# OptoIsolator.net
KiCad netlist of a schematic drawn in Altium Designer
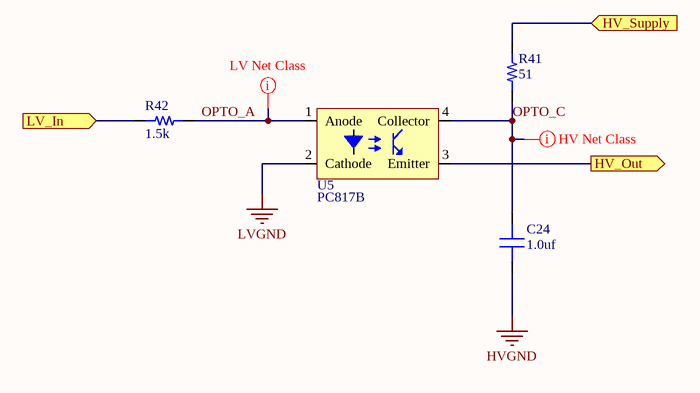
[diagram p0: OptoIsolator.SchDoc]

(export (version "E")
  (design (tool "Eeschema 10.0.6"))
  (components
    (comp (ref "C24")
      (value "1.0uf")
      (footprint "CAP 0603/1608")
      (fields
        (field (name "Comment") "Capacitor MLCC 1.0uf 25V CAP 0603/1608")
        (field (name "CREATED_BY") "Nick Mah")
      )
      (libsource (lib "Altium-Lib") (part "Capacitor"))
    )
    (comp (ref "R41")
      (value "51")
      (footprint "RES 0805/2012")
      (fields
        (field (name "TOLERANCE") "1%")
        (field (name "POWER") "1/4W")
        (field (name "Comment") "Resistor 51 0805 1/4W 1%")
        (field (name "CREATED_BY") "Nick Mah")
      )
      (libsource (lib "Altium-Lib") (part "Resistor"))
    )
    (comp (ref "R42")
      (value "1.5k")
      (footprint "RES 0603/1608")
      (fields
        (field (name "TOLERANCE") "1%")
        (field (name "POWER") "1/10W")
        (field (name "Comment") "Resistor 1.5k 0603 1/10W 1%")
        (field (name "CREATED_BY") "Nick Mah")
      )
      (libsource (lib "Altium-Lib") (part "Resistor"))
    )
    (comp (ref "U5")
      (value "PC817B")
      (footprint "SOIC-4")
      (description "Optoisolator Darlington Output 2500Vrms 1 Channel 4-SSOP")
      (fields (field (name "MFRPARTNO") "PS2802-1-A") (field (name "CREATED_BY") "Nick Mah"))
      (libsource (lib "Altium-Lib") (part "PC817B"))
    )
  )
  (nets
    (net (code "1") (name "/HV_Out") (class "Default")
      (node (ref "U5") (pin "3") (pinfunction "Emitter_3") (pintype "passive"))
    )
    (net (code "2") (name "/HV_Supply") (class "Default")
      (node (ref "R41") (pin "2") (pinfunction "2_2") (pintype "passive"))
    )
    (net (code "3") (name "/LV_In") (class "Default")
      (node (ref "R42") (pin "1") (pinfunction "1_1") (pintype "passive"))
    )
    (net (code "4") (name "/OPTO_A") (class "Default")
      (node (ref "R42") (pin "2") (pinfunction "2_2") (pintype "passive"))
      (node (ref "U5") (pin "1") (pinfunction "Anode_1") (pintype "passive"))
    )
    (net (code "5") (name "/OPTO_C") (class "Default")
      (node (ref "C24") (pin "2") (pinfunction "2_2") (pintype "passive"))
      (node (ref "R41") (pin "1") (pinfunction "1_1") (pintype "passive"))
      (node (ref "U5") (pin "4") (pinfunction "Collector_4") (pintype "passive"))
    )
    (net (code "6") (name "HVGND") (class "Default")
      (node (ref "C24") (pin "1") (pinfunction "1_1") (pintype "passive"))
    )
    (net (code "7") (name "LVGND") (class "Default")
      (node (ref "U5") (pin "2") (pinfunction "Cathode_2") (pintype "passive"))
    )
  )
)
